# Only_pH.net
KiCad netlist of a schematic drawn in Altium Designer
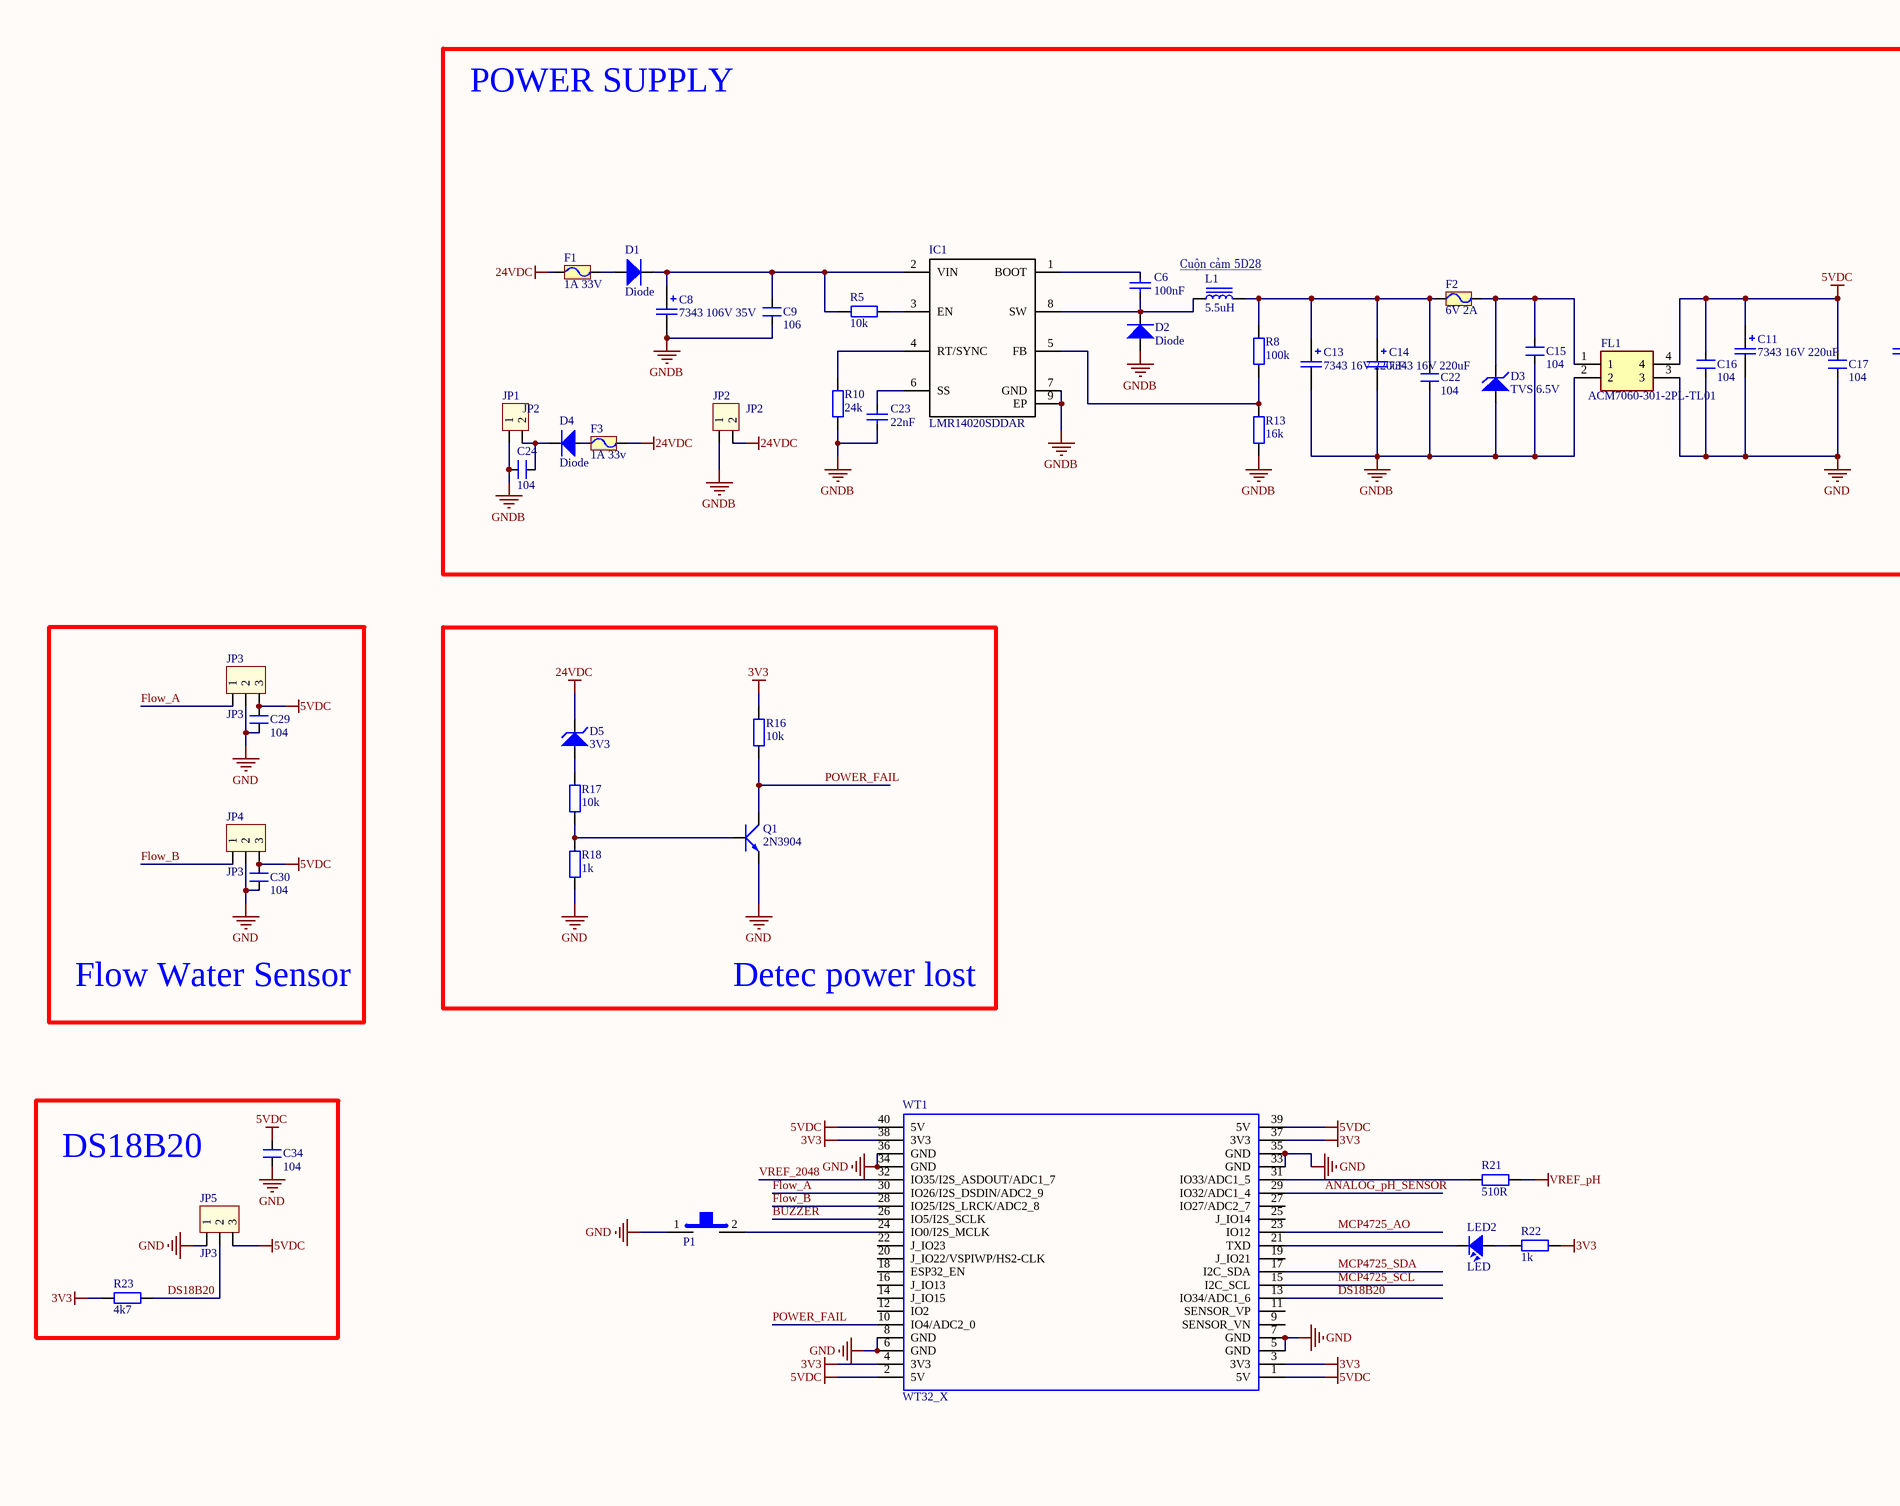
[diagram p0: Only_pH.SchDoc, left]
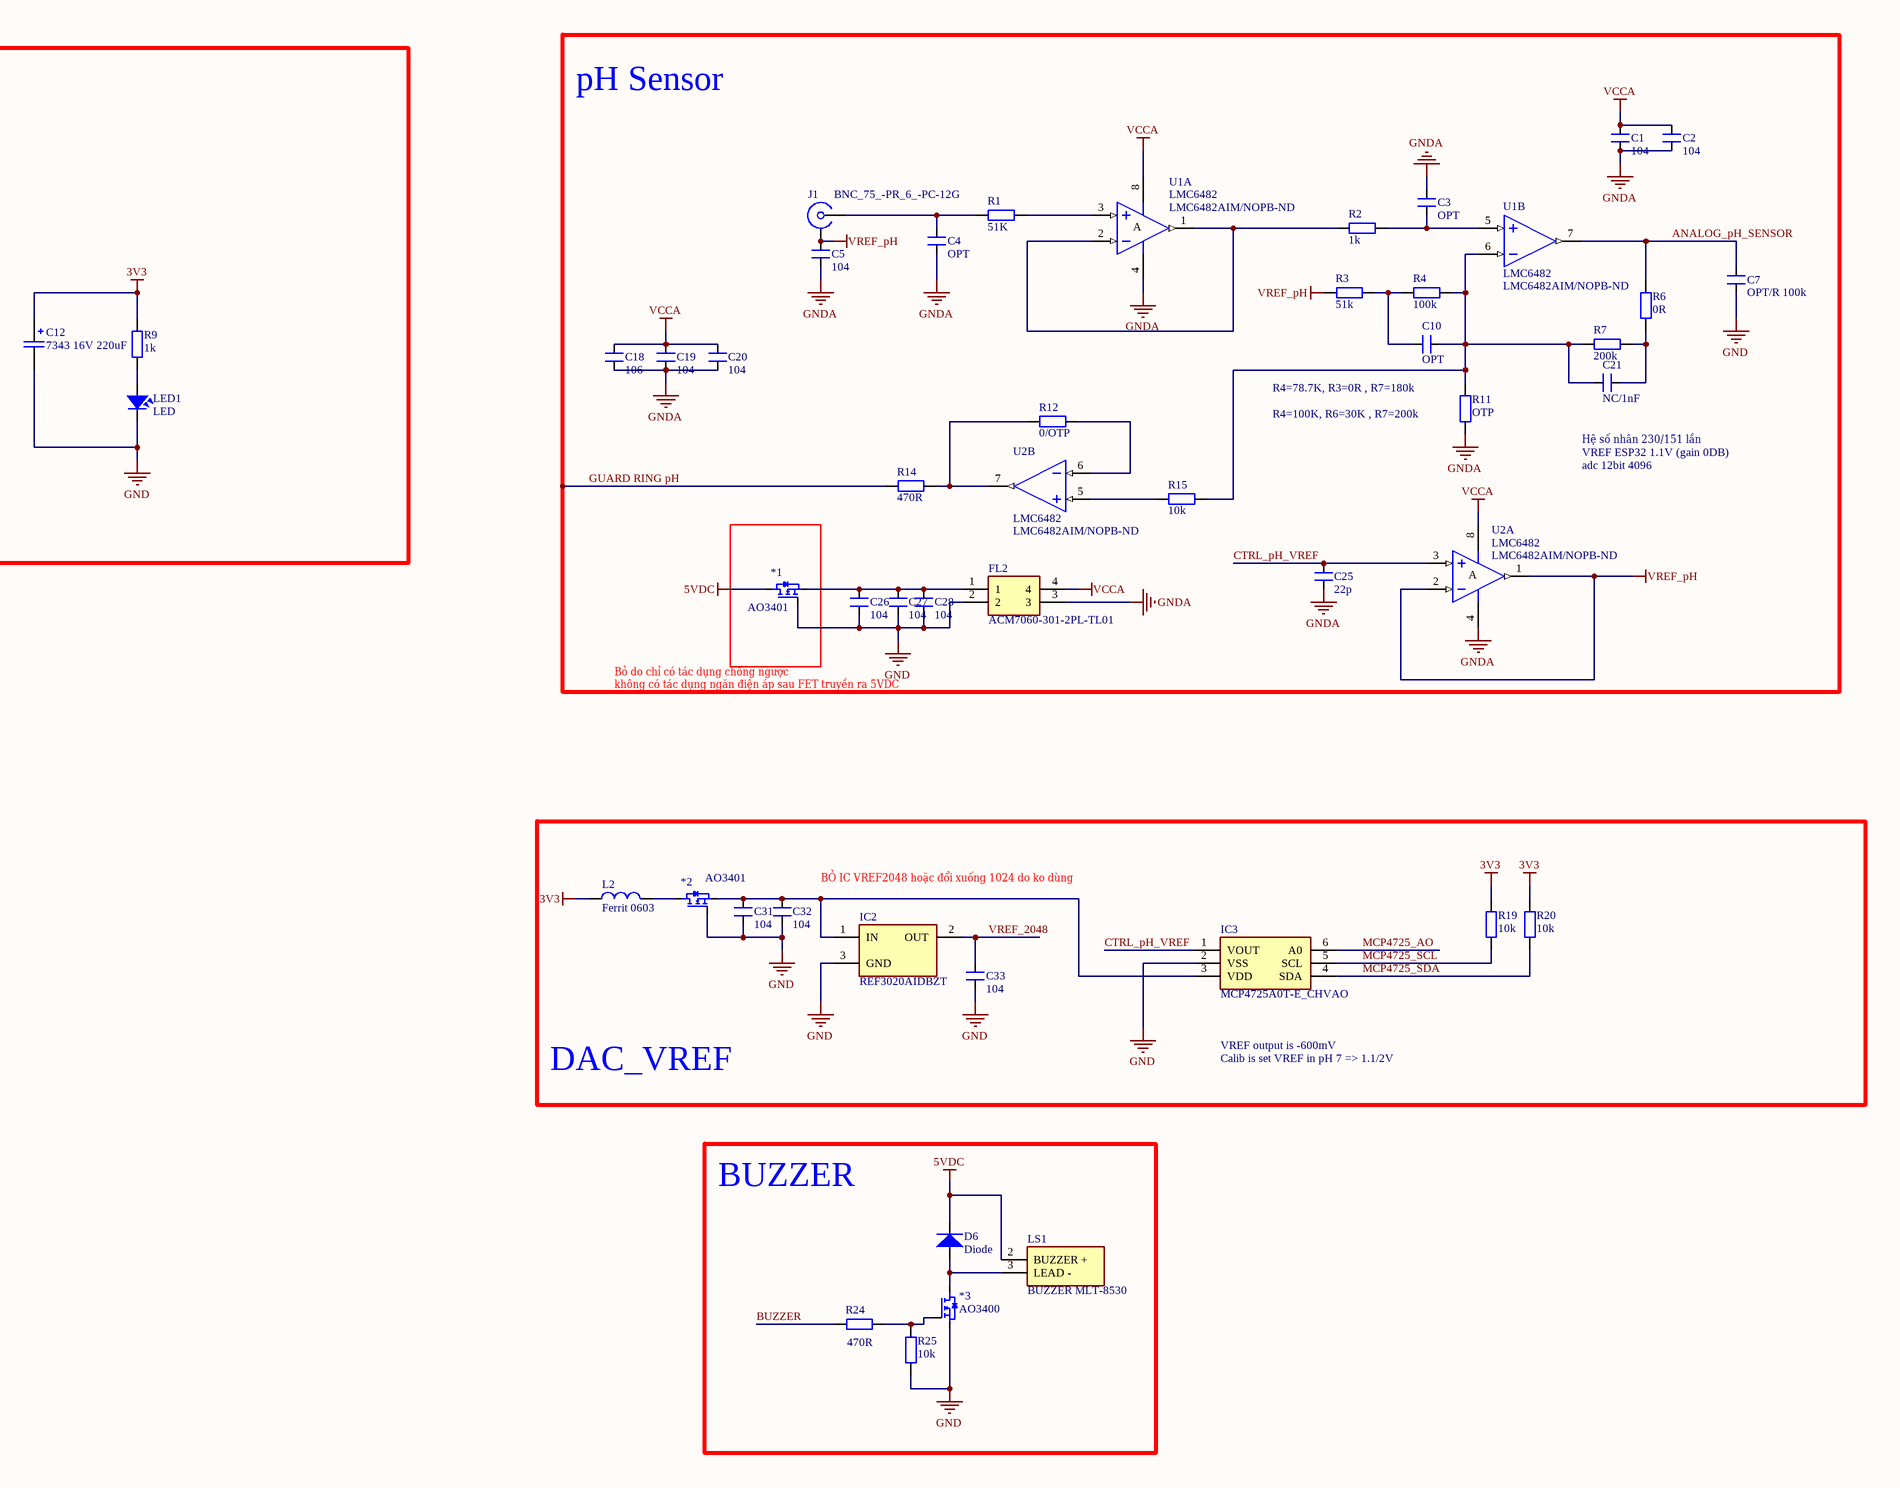
[diagram p1: Only_pH.SchDoc, right]

(export (version "E")
  (design (tool "Eeschema 10.0.6"))
  (components
    (comp (ref "*1") (value "AO3401") (footprint "SOT23-123") (libsource (lib "OBIT_TESLA") (part "AO3401")))
    (comp (ref "*2") (value "AO3401") (footprint "SOT23-123") (libsource (lib "OBIT_TESLA") (part "AO3401")))
    (comp (ref "*3") (value "AO3400") (footprint "SOT23-123") (libsource (lib "OBIT_TESLA") (part "AO3400")))
    (comp (ref "C1")
      (value "104")
      (footprint "SM-0805")
      (description "Cap SMD")
      (libsource (lib "OBIT_TESLA") (part "CM"))
    )
    (comp (ref "C2")
      (value "104")
      (footprint "SM-0805")
      (description "Cap SMD")
      (libsource (lib "OBIT_TESLA") (part "CM"))
    )
    (comp (ref "C3")
      (value "OPT")
      (footprint "CAPC-0603 (1608)")
      (description "Cap SMD")
      (libsource (lib "OBIT_TESLA") (part "CM"))
    )
    (comp (ref "C4")
      (value "OPT")
      (footprint "CAPC-0603 (1608)")
      (description "Cap SMD")
      (libsource (lib "OBIT_TESLA") (part "CM"))
    )
    (comp (ref "C5")
      (value "104")
      (footprint "SM-0805")
      (description "Cap SMD")
      (libsource (lib "OBIT_TESLA") (part "CM"))
    )
    (comp (ref "C6")
      (value "100nF")
      (footprint "SM-0603")
      (libsource (lib "AltiumLibraryTieuBao (1)") (part "CAP_NP"))
    )
    (comp (ref "C7")
      (value "OPT/R 100k")
      (footprint "CAPC-0603 (1608)")
      (description "Cap SMD")
      (libsource (lib "OBIT_TESLA") (part "CM"))
    )
    (comp (ref "C8")
      (value "7343 106V 35V")
      (footprint "CAP_TANTAL_2917(7343-31)")
      (fields (field (name "MPN") "TAJD107K016RNJ"))
      (libsource (lib "BYTECH_HW_LIB_2019") (part "TAJD107K016RNJ"))
    )
    (comp (ref "C9")
      (value "106")
      (footprint "SM-0805")
      (description "Cap SMD")
      (libsource (lib "OBIT_TESLA") (part "CM"))
    )
    (comp (ref "C10")
      (value "OPT")
      (footprint "CAPC-0603 (1608)")
      (description "Cap SMD")
      (libsource (lib "OBIT_TESLA") (part "CM"))
    )
    (comp (ref "C11")
      (value "7343 16V 220uF")
      (footprint "CAP_TANTAL_2917(7343-31)")
      (description "http://linhkienviet.vn/tu-tantalum-16v-220uf-7343")
      (fields (field (name "MPN") "TAJD107K016RNJ"))
      (libsource (lib "BYTECH_HW_LIB_2019") (part "TAJD107K016RNJ"))
    )
    (comp (ref "C12")
      (value "7343 16V 220uF")
      (footprint "CAP_TANTAL_2917(7343-31)")
      (description "http://linhkienviet.vn/tu-tantalum-16v-220uf-7343")
      (fields (field (name "MPN") "TAJD107K016RNJ"))
      (libsource (lib "BYTECH_HW_LIB_2019") (part "TAJD107K016RNJ"))
    )
    (comp (ref "C13")
      (value "7343 16V 220uF")
      (footprint "CAP_TANTAL_2917(7343-31)")
      (description "http://linhkienviet.vn/tu-tantalum-16v-220uf-7343")
      (fields (field (name "MPN") "TAJD107K016RNJ"))
      (libsource (lib "BYTECH_HW_LIB_2019") (part "TAJD107K016RNJ"))
    )
    (comp (ref "C14")
      (value "7343 16V 220uF")
      (footprint "CAP_TANTAL_2917(7343-31)")
      (description "http://linhkienviet.vn/tu-tantalum-16v-220uf-7343")
      (fields (field (name "MPN") "TAJD107K016RNJ"))
      (libsource (lib "BYTECH_HW_LIB_2019") (part "TAJD107K016RNJ"))
    )
    (comp (ref "C15")
      (value "104")
      (footprint "SM-0805")
      (description "Cap SMD")
      (libsource (lib "OBIT_TESLA") (part "CM"))
    )
    (comp (ref "C16")
      (value "104")
      (footprint "SM-0805")
      (description "Cap SMD")
      (libsource (lib "OBIT_TESLA") (part "CM"))
    )
    (comp (ref "C17")
      (value "104")
      (footprint "SM-0805")
      (description "Cap SMD")
      (libsource (lib "OBIT_TESLA") (part "CM"))
    )
    (comp (ref "C18")
      (value "106")
      (footprint "SM-0805")
      (description "Cap SMD")
      (libsource (lib "OBIT_TESLA") (part "CM"))
    )
    (comp (ref "C19")
      (value "104")
      (footprint "SM-0805")
      (description "Cap SMD")
      (libsource (lib "OBIT_TESLA") (part "CM"))
    )
    (comp (ref "C20")
      (value "104")
      (footprint "SM-0805")
      (description "Cap SMD")
      (libsource (lib "OBIT_TESLA") (part "CM"))
    )
    (comp (ref "C21")
      (value "NC/1nF")
      (footprint "CAPC-0603 (1608)")
      (description "Cap SMD")
      (libsource (lib "OBIT_TESLA") (part "CM"))
    )
    (comp (ref "C22")
      (value "104")
      (footprint "SM-0805")
      (description "Cap SMD")
      (libsource (lib "OBIT_TESLA") (part "CM"))
    )
    (comp (ref "C23")
      (value "22nF")
      (footprint "SM-0603")
      (libsource (lib "AltiumLibraryTieuBao (1)") (part "CAP_NP"))
    )
    (comp (ref "C24")
      (value "104")
      (footprint "SM-0805")
      (description "Cap SMD")
      (libsource (lib "OBIT_TESLA") (part "CM"))
    )
    (comp (ref "C25")
      (value "22p")
      (footprint "SM-0805")
      (description "Cap SMD")
      (libsource (lib "OBIT_TESLA") (part "CM"))
    )
    (comp (ref "C26")
      (value "104")
      (footprint "SM-0805")
      (description "Cap SMD")
      (libsource (lib "OBIT_TESLA") (part "CM"))
    )
    (comp (ref "C27")
      (value "104")
      (footprint "SM-0805")
      (description "Cap SMD")
      (libsource (lib "OBIT_TESLA") (part "CM"))
    )
    (comp (ref "C28")
      (value "104")
      (footprint "SM-0805")
      (description "Cap SMD")
      (libsource (lib "OBIT_TESLA") (part "CM"))
    )
    (comp (ref "C29")
      (value "104")
      (footprint "SM-0805")
      (description "Cap SMD")
      (libsource (lib "OBIT_TESLA") (part "CM"))
    )
    (comp (ref "C30")
      (value "104")
      (footprint "SM-0805")
      (description "Cap SMD")
      (libsource (lib "OBIT_TESLA") (part "CM"))
    )
    (comp (ref "C31")
      (value "104")
      (footprint "SM-0805")
      (description "Cap SMD")
      (libsource (lib "OBIT_TESLA") (part "CM"))
    )
    (comp (ref "C32")
      (value "104")
      (footprint "SM-0805")
      (description "Cap SMD")
      (libsource (lib "OBIT_TESLA") (part "CM"))
    )
    (comp (ref "C33")
      (value "104")
      (footprint "SM-0603")
      (description "Cap SMD")
      (libsource (lib "OBIT_TESLA") (part "CM"))
    )
    (comp (ref "C34")
      (value "104")
      (footprint "SM-0805")
      (description "Cap SMD")
      (libsource (lib "OBIT_TESLA") (part "CM"))
    )
    (comp (ref "D1") (value "Diode") (footprint "DIO-SMD-106") (libsource (lib "OBIT_TESLA") (part "Diode")))
    (comp (ref "D2") (value "Diode") (footprint "DIO-SMD-106") (libsource (lib "OBIT_TESLA") (part "Diode")))
    (comp (ref "D3")
      (value "TVS 6.5V")
      (footprint "DIO-SMD-106")
      (description "Diode Zener")
      (fields (field (name "PART NUMBER") "BZV55-C5V1"))
      (libsource (lib "OBIT_TESLA") (part "Diode Zener"))
    )
    (comp (ref "D4") (value "Diode") (footprint "DIO-SMD-106") (libsource (lib "OBIT_TESLA") (part "Diode")))
    (comp (ref "D5")
      (value "3V3")
      (footprint "DIO-SMD-106")
      (description "Diode Zener")
      (fields (field (name "PART NUMBER") "BZV55-C5V1"))
      (libsource (lib "OBIT_TESLA") (part "Diode Zener"))
    )
    (comp (ref "D6") (value "Diode") (footprint "DIO-SMD-123") (libsource (lib "") (part "Diode_1")))
    (comp (ref "F1")
      (value "1A 33V")
      (footprint "RES-SMD-1812")
      (libsource (lib "OBIT_TESLA") (part "FUSE_1"))
    )
    (comp (ref "F2")
      (value "6V 2A")
      (footprint "RES-SMD-1812")
      (libsource (lib "OBIT_TESLA") (part "FUSE_1"))
    )
    (comp (ref "F3")
      (value "1A 33v")
      (footprint "RES-SMD-1812")
      (libsource (lib "OBIT_TESLA") (part "FUSE_1"))
    )
    (comp (ref "FL1")
      (value "ACM7060-301-2PL-TL01")
      (footprint "ACM70603012PLTL01")
      (description "Filter")
      (fields (field (name "MOUSER PART NUMBER") "810-ACM7063012PLTL01"))
      (libsource (lib "OBIT_TESLA") (part "ACM7060-301-2PL-TL01"))
    )
    (comp (ref "FL2")
      (value "ACM7060-301-2PL-TL01")
      (footprint "ACM70603012PLTL01")
      (description "Filter")
      (fields (field (name "MOUSER PART NUMBER") "810-ACM7063012PLTL01"))
      (libsource (lib "OBIT_TESLA") (part "ACM7060-301-2PL-TL01"))
    )
    (comp (ref "IC1")
      (value "LMR14020SDDAR")
      (footprint "SOIC127P600X170-9N")
      (description "Integrated Circuit")
      (fields (field (name "MOUSER PART NUMBER") "595-LMR14020SDDAR"))
      (libsource (lib "OBIT_TESLA") (part "LMR14020SDDAR"))
    )
    (comp (ref "IC2")
      (value "REF3020AIDBZT")
      (footprint "SOT95P237X112-3N")
      (description "Integrated Circuit")
      (fields (field (name "MOUSER PART NUMBER") "595-REF3020AIDBZT"))
      (libsource (lib "OBIT_TESLA") (part "REF3020AIDBZT"))
    )
    (comp (ref "IC3")
      (value "MCP4725A0T-E_CHVAO")
      (footprint "SOT95P270X145-6N")
      (description "Integrated Circuit")
      (fields
        (field (name "MANUFACTURER_PART_NUMBER") "MCP4725A0T-E/CHVAO")
        (field (name "MOUSER PART NUMBER") "579-MCP4725A0TECHVAO")
      )
      (libsource (lib "OBIT_TESLA") (part "MCP4725A0T-E_CHVAO"))
    )
    (comp (ref "J1")
      (value "BNC_75_-PR_6_-PC-12G")
      (footprint "BNC75PR6PC12G")
      (description "Connector")
      (fields
        (field (name "MANUFACTURER_PART_NUMBER") "BNC(75)-PR(6)-PC-12G")
        (field (name "MOUSER PART NUMBER") "798-BNC75-PR6-PC-12G")
      )
      (libsource (lib "OBIT_TESLA") (part "BNC_75_-PR_6_-PC-12G"))
    )
    (comp (ref "JP1")
      (value "JP2")
      (footprint "CON2")
      (description "Connector 2")
      (libsource (lib "OBIT_TESLA") (part "Con2"))
    )
    (comp (ref "JP2")
      (value "JP2")
      (footprint "CON2")
      (description "Connector 2")
      (libsource (lib "OBIT_TESLA") (part "Con2"))
    )
    (comp (ref "JP3")
      (value "JP3")
      (footprint "CON3")
      (description "Connector 3")
      (libsource (lib "OBIT_TESLA") (part "Con3"))
    )
    (comp (ref "JP4")
      (value "JP3")
      (footprint "CON3")
      (description "Connector 3")
      (libsource (lib "OBIT_TESLA") (part "Con3"))
    )
    (comp (ref "JP5")
      (value "JP3")
      (footprint "CON3")
      (description "Connector 3")
      (libsource (lib "OBIT_TESLA") (part "Con3"))
    )
    (comp (ref "L1")
      (value "5.5uH")
      (footprint "WURTH WE-HCI 7040")
      (description "SMT Inductor")
      (libsource (lib "OBIT_TESLA") (part "Inductor_3"))
    )
    (comp (ref "L2")
      (value "Ferrit 0603")
      (footprint "IND-0603 (1608)")
      (description "FIXED IND 10UH 60MA 700 MOHM SMD")
      (fields (field (name "MPN") "LB1608T100M"))
      (libsource (lib "OBIT_TESLA") (part "LB1608T100M"))
    )
    (comp (ref "LED1")
      (value "LED")
      (footprint "SM-LED-0805-Blue")
      (libsource (lib "OBIT_TESLA") (part "LED"))
    )
    (comp (ref "LED2")
      (value "LED")
      (footprint "SM-LED-0805-Blue")
      (libsource (lib "OBIT_TESLA") (part "LED"))
    )
    (comp (ref "LS1")
      (value "BUZZER MLT-8530")
      (footprint "MLT8530")
      (description "Loudspeaker or Buzzer")
      (fields (field (name "MANUFACTURER_PART_NUMBER") "MLT-8530"))
      (libsource (lib "OBIT_TESLA") (part "BUZZER MLT-8530"))
    )
    (comp (ref "P1")
      (value "~")
      (footprint "SW 2P SMD")
      (description "SMD Mini Push Button Switch 2 Pin 3x6x2.7mm")
      (fields (field (name "MPN") "SMD Mini Push Button 2 SMD"))
      (libsource (lib "OBIT_TESLA") (part "Button 2 SMD"))
    )
    (comp (ref "Q1")
      (value "2N3904")
      (footprint "SOT23-231")
      (description "NPN 600mW, ECB")
      (libsource (lib "OBIT_TESLA") (part "2N3904"))
    )
    (comp (ref "R1")
      (value "51K")
      (footprint "RES-SMD-0603")
      (description "Resistor R1/4W")
      (libsource (lib "OBIT_TESLA") (part "R"))
    )
    (comp (ref "R2")
      (value "1k")
      (footprint "RES-SMD-0603")
      (description "Resistor R1/4W")
      (libsource (lib "OBIT_TESLA") (part "R"))
    )
    (comp (ref "R3")
      (value "51k")
      (footprint "RES-SMD-0603")
      (description "Resistor R1/4W")
      (libsource (lib "OBIT_TESLA") (part "R"))
    )
    (comp (ref "R4")
      (value "100k")
      (footprint "RES-SMD-0603")
      (description "Resistor R1/4W")
      (libsource (lib "OBIT_TESLA") (part "R"))
    )
    (comp (ref "R5")
      (value "10k")
      (footprint "RES-SMD-0603")
      (description "Resistor R1/4W")
      (libsource (lib "OBIT_TESLA") (part "R"))
    )
    (comp (ref "R6")
      (value "0R")
      (footprint "RES-SMD-0603")
      (description "Resistor R1/4W")
      (libsource (lib "OBIT_TESLA") (part "R"))
    )
    (comp (ref "R7")
      (value "200k")
      (footprint "RES-SMD-0603")
      (description "Resistor R1/4W")
      (libsource (lib "OBIT_TESLA") (part "R"))
    )
    (comp (ref "R8")
      (value "100k")
      (footprint "RES-SMD-0603")
      (description "Resistor R1/4W")
      (libsource (lib "OBIT_TESLA") (part "R"))
    )
    (comp (ref "R9")
      (value "1k")
      (footprint "RES-SMD-0603")
      (description "Resistor R1/4W")
      (libsource (lib "OBIT_TESLA") (part "R"))
    )
    (comp (ref "R10")
      (value "24k")
      (footprint "RES-SMD-0603")
      (description "Resistor R1/4W")
      (libsource (lib "OBIT_TESLA") (part "R"))
    )
    (comp (ref "R11")
      (value "OTP")
      (footprint "RES-SMD-0603")
      (description "Resistor R1/4W")
      (libsource (lib "OBIT_TESLA") (part "R"))
    )
    (comp (ref "R12")
      (value "0/OTP")
      (footprint "RES-SMD-0603")
      (description "Resistor R1/4W")
      (libsource (lib "OBIT_TESLA") (part "R"))
    )
    (comp (ref "R13")
      (value "16k")
      (footprint "RES-SMD-0603")
      (description "Resistor R1/4W")
      (libsource (lib "OBIT_TESLA") (part "R"))
    )
    (comp (ref "R14")
      (value "470R")
      (footprint "RES-SMD-0603")
      (description "Resistor R1/4W")
      (libsource (lib "OBIT_TESLA") (part "R"))
    )
    (comp (ref "R15")
      (value "10k")
      (footprint "RES-SMD-0603")
      (description "Resistor R1/4W")
      (libsource (lib "OBIT_TESLA") (part "R"))
    )
    (comp (ref "R16")
      (value "10k")
      (footprint "RES-SMD-0603")
      (description "Resistor R1/4W")
      (libsource (lib "OBIT_TESLA") (part "R"))
    )
    (comp (ref "R17")
      (value "10k")
      (footprint "RES-SMD-0603")
      (description "Resistor R1/4W")
      (libsource (lib "OBIT_TESLA") (part "R"))
    )
    (comp (ref "R18")
      (value "1k")
      (footprint "RES-SMD-0603")
      (description "Resistor R1/4W")
      (libsource (lib "OBIT_TESLA") (part "R"))
    )
    (comp (ref "R19")
      (value "10k")
      (footprint "RES-SMD-0603")
      (description "Resistor R1/4W")
      (libsource (lib "OBIT_TESLA") (part "R"))
    )
    (comp (ref "R20")
      (value "10k")
      (footprint "RES-SMD-0603")
      (description "Resistor R1/4W")
      (libsource (lib "OBIT_TESLA") (part "R"))
    )
    (comp (ref "R21")
      (value "510R")
      (footprint "RES-SMD-0603")
      (description "Resistor R1/4W")
      (libsource (lib "OBIT_TESLA") (part "R"))
    )
    (comp (ref "R22")
      (value "1k")
      (footprint "RES-SMD-0603")
      (description "Resistor R1/4W")
      (libsource (lib "OBIT_TESLA") (part "R"))
    )
    (comp (ref "R23")
      (value "4k7")
      (footprint "RES-SMD-0603")
      (description "Resistor R1/4W")
      (libsource (lib "OBIT_TESLA") (part "R"))
    )
    (comp (ref "R24")
      (value "470R")
      (footprint "RES-SMD-0603")
      (description "Resistor R1/4W")
      (libsource (lib "OBIT_TESLA") (part "R"))
    )
    (comp (ref "R25")
      (value "10k")
      (footprint "RES-SMD-0603")
      (description "Resistor R1/4W")
      (libsource (lib "OBIT_TESLA") (part "R"))
    )
    (comp (ref "U1")
      (value "LMC6482")
      (footprint "SOIC-8")
      (description "LMC6482 CMOS Dual Rail-to-Rail Input and Output Operational Amplifier")
      (fields (field (name "MFR") "Ti") (field (name "SUPPLIER PART NUMBER 1") "LMC6482AIM/NOPB-ND"))
      (libsource (lib "OBIT_TESLA") (part "LMC6482"))
    )
    (comp (ref "U2")
      (value "LMC6482")
      (footprint "SOIC-8")
      (description "LMC6482 CMOS Dual Rail-to-Rail Input and Output Operational Amplifier")
      (fields (field (name "MFR") "Ti") (field (name "SUPPLIER PART NUMBER 1") "LMC6482AIM/NOPB-ND"))
      (libsource (lib "OBIT_TESLA") (part "LMC6482"))
    )
    (comp (ref "WT1")
      (value "WT32_X")
      (footprint "WT32_SC01_Sheild")
      (libsource (lib "OBIT_TESLA") (part "WT32-SC01"))
    )
  )
  (nets
    (net (code "1") (name "/ANALOG_pH_SENSOR") (class "Default")
      (node (ref "C7") (pin "1") (pinfunction "1_1") (pintype "passive"))
      (node (ref "R6") (pin "1") (pinfunction "1_1") (pintype "passive"))
      (node (ref "U1") (pin "7") (pinfunction "OUT_7") (pintype "output"))
      (node (ref "WT1") (pin "29") (pinfunction "IO32/ADC1_4_29") (pintype "passive"))
    )
    (net (code "2") (name "/BUZZER") (class "Default")
      (node (ref "R24") (pin "2") (pinfunction "2_2") (pintype "passive"))
      (node (ref "WT1") (pin "26") (pinfunction "IO5/I2S_SCLK_26") (pintype "passive"))
    )
    (net (code "3") (name "/CTRL_pH_VREF") (class "Default")
      (node (ref "C25") (pin "1") (pinfunction "1_1") (pintype "passive"))
      (node (ref "IC3") (pin "1") (pinfunction "VOUT_1") (pintype "passive"))
      (node (ref "U2") (pin "3") (pinfunction "IN+_3") (pintype "input"))
    )
    (net (code "5") (name "/DS18B20") (class "Default")
      (node (ref "JP5") (pin "2") (pinfunction "2_2") (pintype "passive"))
      (node (ref "R23") (pin "2") (pinfunction "2_2") (pintype "passive"))
      (node (ref "WT1") (pin "13") (pinfunction "IO34/ADC1_6_13") (pintype "passive"))
    )
    (net (code "8") (name "/Flow_A") (class "Default")
      (node (ref "JP3") (pin "1") (pinfunction "1_1") (pintype "passive"))
      (node (ref "WT1") (pin "30") (pinfunction "IO26/I2S_DSDIN/ADC2_9_30") (pintype "passive"))
    )
    (net (code "9") (name "/Flow_B") (class "Default")
      (node (ref "JP4") (pin "1") (pinfunction "1_1") (pintype "passive"))
      (node (ref "WT1") (pin "28") (pinfunction "IO25/I2S_LRCK/ADC2_8_28") (pintype "passive"))
    )
    (net (code "10") (name "/GUARD RING pH") (class "Default")
      (node (ref "R14") (pin "2") (pinfunction "2_2") (pintype "passive"))
    )
    (net (code "11") (name "/MCP4725_AO") (class "Default")
      (node (ref "IC3") (pin "6") (pinfunction "A0_6") (pintype "passive"))
      (node (ref "WT1") (pin "23") (pinfunction "IO12_23") (pintype "passive"))
    )
    (net (code "12") (name "/MCP4725_SCL") (class "Default")
      (node (ref "IC3") (pin "5") (pinfunction "SCL_5") (pintype "passive"))
      (node (ref "R19") (pin "2") (pinfunction "2_2") (pintype "passive"))
      (node (ref "WT1") (pin "15") (pinfunction "I2C_SCL_15") (pintype "passive"))
    )
    (net (code "13") (name "/MCP4725_SDA") (class "Default")
      (node (ref "IC3") (pin "4") (pinfunction "SDA_4") (pintype "passive"))
      (node (ref "R20") (pin "2") (pinfunction "2_2") (pintype "passive"))
      (node (ref "WT1") (pin "17") (pinfunction "I2C_SDA_17") (pintype "passive"))
    )
    (net (code "15") (name "/POWER_FAIL") (class "Default")
      (node (ref "Q1") (pin "3") (pinfunction "C_3") (pintype "passive"))
      (node (ref "R16") (pin "2") (pinfunction "2_2") (pintype "passive"))
      (node (ref "WT1") (pin "10") (pinfunction "IO4/ADC2_0_10") (pintype "passive"))
    )
    (net (code "16") (name "/VREF_2048") (class "Default")
      (node (ref "C33") (pin "2") (pinfunction "2_2") (pintype "passive"))
      (node (ref "IC2") (pin "2") (pinfunction "OUT_2") (pintype "passive"))
      (node (ref "WT1") (pin "32") (pinfunction "IO35/I2S_ASDOUT/ADC1_7_32") (pintype "passive"))
    )
    (net (code "18") (name "3V3") (class "Default")
      (node (ref "C12") (pin "1") (pinfunction "1_1") (pintype "passive"))
      (node (ref "L2") (pin "1") (pinfunction "1_1") (pintype "passive"))
      (node (ref "R16") (pin "1") (pinfunction "1_1") (pintype "passive"))
      (node (ref "R19") (pin "1") (pinfunction "1_1") (pintype "passive"))
      (node (ref "R20") (pin "1") (pinfunction "1_1") (pintype "passive"))
      (node (ref "R22") (pin "2") (pinfunction "2_2") (pintype "passive"))
      (node (ref "R23") (pin "1") (pinfunction "1_1") (pintype "passive"))
      (node (ref "R9") (pin "2") (pinfunction "2_2") (pintype "passive"))
      (node (ref "WT1") (pin "3") (pinfunction "3V3_3") (pintype "passive"))
      (node (ref "WT1") (pin "37") (pinfunction "3V3_37") (pintype "passive"))
      (node (ref "WT1") (pin "38") (pinfunction "3V3_38") (pintype "passive"))
      (node (ref "WT1") (pin "4") (pinfunction "3V3_4") (pintype "passive"))
    )
    (net (code "19") (name "5VDC") (class "Default")
      (node (ref "*1") (pin "2") (pintype "passive"))
      (node (ref "C11") (pin "1") (pinfunction "1_1") (pintype "passive"))
      (node (ref "C16") (pin "2") (pinfunction "2_2") (pintype "passive"))
      (node (ref "C17") (pin "2") (pinfunction "2_2") (pintype "passive"))
      (node (ref "C29") (pin "2") (pinfunction "2_2") (pintype "passive"))
      (node (ref "C30") (pin "2") (pinfunction "2_2") (pintype "passive"))
      (node (ref "C34") (pin "2") (pinfunction "2_2") (pintype "passive"))
      (node (ref "D6") (pin "2") (pinfunction "2_2") (pintype "passive"))
      (node (ref "FL1") (pin "4") (pinfunction "4_4") (pintype "passive"))
      (node (ref "JP3") (pin "3") (pinfunction "3_3") (pintype "passive"))
      (node (ref "JP4") (pin "3") (pinfunction "3_3") (pintype "passive"))
      (node (ref "JP5") (pin "3") (pinfunction "3_3") (pintype "passive"))
      (node (ref "LS1") (pin "2") (pinfunction "BUZZER_+_2") (pintype "passive"))
      (node (ref "WT1") (pin "1") (pinfunction "5V_1") (pintype "passive"))
      (node (ref "WT1") (pin "2") (pinfunction "5V_2") (pintype "passive"))
      (node (ref "WT1") (pin "39") (pinfunction "5V_39") (pintype "passive"))
      (node (ref "WT1") (pin "40") (pinfunction "5V_40") (pintype "passive"))
    )
    (net (code "20") (name "24VDC") (class "Default")
      (node (ref "D5") (pin "2") (pinfunction "2_2") (pintype "passive"))
      (node (ref "F1") (pin "2") (pinfunction "2_2") (pintype "passive"))
      (node (ref "F3") (pin "1") (pinfunction "1_1") (pintype "passive"))
      (node (ref "JP2") (pin "2") (pinfunction "2_2") (pintype "passive"))
    )
    (net (code "21") (name "GND") (class "Default")
      (node (ref "*1") (pin "1") (pintype "passive"))
      (node (ref "*2") (pin "1") (pintype "passive"))
      (node (ref "*3") (pin "3") (pintype "passive"))
      (node (ref "C11") (pin "2") (pinfunction "2_2") (pintype "passive"))
      (node (ref "C12") (pin "2") (pinfunction "2_2") (pintype "passive"))
      (node (ref "C16") (pin "1") (pinfunction "1_1") (pintype "passive"))
      (node (ref "C17") (pin "1") (pinfunction "1_1") (pintype "passive"))
      (node (ref "C26") (pin "2") (pinfunction "2_2") (pintype "passive"))
      (node (ref "C27") (pin "2") (pinfunction "2_2") (pintype "passive"))
      (node (ref "C28") (pin "2") (pinfunction "2_2") (pintype "passive"))
      (node (ref "C29") (pin "1") (pinfunction "1_1") (pintype "passive"))
      (node (ref "C30") (pin "1") (pinfunction "1_1") (pintype "passive"))
      (node (ref "C31") (pin "2") (pinfunction "2_2") (pintype "passive"))
      (node (ref "C32") (pin "2") (pinfunction "2_2") (pintype "passive"))
      (node (ref "C33") (pin "1") (pinfunction "1_1") (pintype "passive"))
      (node (ref "C34") (pin "1") (pinfunction "1_1") (pintype "passive"))
      (node (ref "C7") (pin "2") (pinfunction "2_2") (pintype "passive"))
      (node (ref "FL1") (pin "3") (pinfunction "3_3") (pintype "passive"))
      (node (ref "FL2") (pin "2") (pinfunction "2_2") (pintype "passive"))
      (node (ref "IC2") (pin "3") (pinfunction "GND_3") (pintype "passive"))
      (node (ref "IC3") (pin "2") (pinfunction "VSS_2") (pintype "passive"))
      (node (ref "JP3") (pin "2") (pinfunction "2_2") (pintype "passive"))
      (node (ref "JP4") (pin "2") (pinfunction "2_2") (pintype "passive"))
      (node (ref "JP5") (pin "1") (pinfunction "1_1") (pintype "passive"))
      (node (ref "LED1") (pin "2") (pinfunction "2_2") (pintype "passive"))
      (node (ref "P1") (pin "1") (pinfunction "1_1") (pintype "passive"))
      (node (ref "Q1") (pin "1") (pinfunction "E_1") (pintype "passive"))
      (node (ref "R18") (pin "2") (pinfunction "2_2") (pintype "passive"))
      (node (ref "R25") (pin "1") (pinfunction "1_1") (pintype "passive"))
      (node (ref "WT1") (pin "33") (pinfunction "GND_33") (pintype "passive"))
      (node (ref "WT1") (pin "34") (pinfunction "GND_34") (pintype "passive"))
      (node (ref "WT1") (pin "35") (pinfunction "GND_35") (pintype "passive"))
      (node (ref "WT1") (pin "36") (pinfunction "GND_36") (pintype "passive"))
      (node (ref "WT1") (pin "5") (pinfunction "GND_5") (pintype "passive"))
      (node (ref "WT1") (pin "6") (pinfunction "GND_6") (pintype "passive"))
      (node (ref "WT1") (pin "7") (pinfunction "GND_7") (pintype "passive"))
      (node (ref "WT1") (pin "8") (pinfunction "GND_8") (pintype "passive"))
    )
    (net (code "22") (name "GNDA") (class "Default")
      (node (ref "C1") (pin "2") (pinfunction "2_2") (pintype "passive"))
      (node (ref "C18") (pin "2") (pinfunction "2_2") (pintype "passive"))
      (node (ref "C19") (pin "2") (pinfunction "2_2") (pintype "passive"))
      (node (ref "C2") (pin "2") (pinfunction "2_2") (pintype "passive"))
      (node (ref "C20") (pin "2") (pinfunction "2_2") (pintype "passive"))
      (node (ref "C25") (pin "2") (pinfunction "2_2") (pintype "passive"))
      (node (ref "C3") (pin "1") (pinfunction "1_1") (pintype "passive"))
      (node (ref "C4") (pin "2") (pinfunction "2_2") (pintype "passive"))
      (node (ref "C5") (pin "1") (pinfunction "1_1") (pintype "passive"))
      (node (ref "FL2") (pin "3") (pinfunction "3_3") (pintype "passive"))
      (node (ref "R11") (pin "2") (pinfunction "2_2") (pintype "passive"))
      (node (ref "U1") (pin "4") (pinfunction "V-_4") (pintype "power_in"))
      (node (ref "U2") (pin "4") (pinfunction "V-_4") (pintype "power_in"))
    )
    (net (code "23") (name "GNDB") (class "Default")
      (node (ref "C13") (pin "2") (pinfunction "2_2") (pintype "passive"))
      (node (ref "C14") (pin "2") (pinfunction "2_2") (pintype "passive"))
      (node (ref "C15") (pin "1") (pinfunction "1_1") (pintype "passive"))
      (node (ref "C22") (pin "1") (pinfunction "1_1") (pintype "passive"))
      (node (ref "C23") (pin "1") (pinfunction "1_1") (pintype "passive"))
      (node (ref "C24") (pin "2") (pinfunction "2_2") (pintype "passive"))
      (node (ref "C8") (pin "2") (pinfunction "2_2") (pintype "passive"))
      (node (ref "C9") (pin "1") (pinfunction "1_1") (pintype "passive"))
      (node (ref "D2") (pin "1") (pinfunction "1_1") (pintype "passive"))
      (node (ref "D3") (pin "1") (pinfunction "1_1") (pintype "passive"))
      (node (ref "FL1") (pin "2") (pinfunction "2_2") (pintype "passive"))
      (node (ref "IC1") (pin "7") (pinfunction "GND_7") (pintype "passive"))
      (node (ref "IC1") (pin "9") (pinfunction "EP_9") (pintype "passive"))
      (node (ref "JP1") (pin "1") (pinfunction "1_1") (pintype "passive"))
      (node (ref "JP2") (pin "1") (pinfunction "1_1") (pintype "passive"))
      (node (ref "R10") (pin "1") (pinfunction "1_1") (pintype "passive"))
      (node (ref "R13") (pin "2") (pinfunction "2_2") (pintype "passive"))
    )
    (net (code "24") (name "Net-(*1-Pad3)") (class "Default")
      (node (ref "*1") (pin "3") (pintype "passive"))
      (node (ref "C26") (pin "1") (pinfunction "1_1") (pintype "passive"))
      (node (ref "C27") (pin "1") (pinfunction "1_1") (pintype "passive"))
      (node (ref "C28") (pin "1") (pinfunction "1_1") (pintype "passive"))
      (node (ref "FL2") (pin "1") (pinfunction "1_1") (pintype "passive"))
    )
    (net (code "25") (name "Net-(*2-Pad2)") (class "Default")
      (node (ref "*2") (pin "2") (pintype "passive"))
      (node (ref "L2") (pin "2") (pinfunction "2_2") (pintype "passive"))
    )
    (net (code "26") (name "Net-(*3-Pad1)") (class "Default")
      (node (ref "*3") (pin "1") (pintype "passive"))
      (node (ref "R24") (pin "1") (pinfunction "1_1") (pintype "passive"))
      (node (ref "R25") (pin "2") (pinfunction "2_2") (pintype "passive"))
    )
    (net (code "27") (name "Net-(C4-Pad1)") (class "Default")
      (node (ref "C4") (pin "1") (pinfunction "1_1") (pintype "passive"))
      (node (ref "J1") (pin "1") (pinfunction "1_1") (pintype "passive"))
      (node (ref "R1") (pin "2") (pinfunction "2_2") (pintype "passive"))
    )
    (net (code "28") (name "Net-(C10-Pad1)") (class "Default")
      (node (ref "C10") (pin "1") (pinfunction "1_1") (pintype "passive"))
      (node (ref "R3") (pin "1") (pinfunction "1_1") (pintype "passive"))
      (node (ref "R4") (pin "2") (pinfunction "2_2") (pintype "passive"))
    )
    (net (code "29") (name "Net-(C13-Pad1)") (class "Default")
      (node (ref "C13") (pin "1") (pinfunction "1_1") (pintype "passive"))
      (node (ref "C14") (pin "1") (pinfunction "1_1") (pintype "passive"))
      (node (ref "C22") (pin "2") (pinfunction "2_2") (pintype "passive"))
      (node (ref "F2") (pin "2") (pinfunction "2_2") (pintype "passive"))
      (node (ref "L1") (pin "2") (pinfunction "2_2") (pintype "passive"))
      (node (ref "R8") (pin "1") (pinfunction "1_1") (pintype "passive"))
    )
    (net (code "30") (name "Net-(C15-Pad2)") (class "Default")
      (node (ref "C15") (pin "2") (pinfunction "2_2") (pintype "passive"))
      (node (ref "D3") (pin "2") (pinfunction "2_2") (pintype "passive"))
      (node (ref "F2") (pin "1") (pinfunction "1_1") (pintype "passive"))
      (node (ref "FL1") (pin "1") (pinfunction "1_1") (pintype "passive"))
    )
    (net (code "31") (name "Net-(C21-Pad2)") (class "Default")
      (node (ref "C21") (pin "2") (pinfunction "2_2") (pintype "passive"))
      (node (ref "R6") (pin "2") (pinfunction "2_2") (pintype "passive"))
      (node (ref "R7") (pin "1") (pinfunction "1_1") (pintype "passive"))
    )
    (net (code "32") (name "Net-(C24-Pad1)") (class "Default")
      (node (ref "C24") (pin "1") (pinfunction "1_1") (pintype "passive"))
      (node (ref "D4") (pin "2") (pinfunction "2_2") (pintype "passive"))
      (node (ref "JP1") (pin "2") (pinfunction "2_2") (pintype "passive"))
    )
    (net (code "33") (name "Net-(D1-Pad1)") (class "Default")
      (node (ref "D1") (pin "1") (pinfunction "1_1") (pintype "passive"))
      (node (ref "F1") (pin "1") (pinfunction "1_1") (pintype "passive"))
    )
    (net (code "34") (name "Net-(D4-Pad1)") (class "Default")
      (node (ref "D4") (pin "1") (pinfunction "1_1") (pintype "passive"))
      (node (ref "F3") (pin "2") (pinfunction "2_2") (pintype "passive"))
    )
    (net (code "35") (name "Net-(D5-Pad1)") (class "Default")
      (node (ref "D5") (pin "1") (pinfunction "1_1") (pintype "passive"))
      (node (ref "R17") (pin "2") (pinfunction "2_2") (pintype "passive"))
    )
    (net (code "36") (name "Net-(IC1-BOOT)") (class "Default")
      (node (ref "C6") (pin "2") (pinfunction "2_2") (pintype "passive"))
      (node (ref "IC1") (pin "1") (pinfunction "BOOT_1") (pintype "passive"))
    )
    (net (code "37") (name "Net-(IC1-EN)") (class "Default")
      (node (ref "IC1") (pin "3") (pinfunction "EN_3") (pintype "passive"))
      (node (ref "R5") (pin "2") (pinfunction "2_2") (pintype "passive"))
    )
    (net (code "38") (name "Net-(IC1-FB)") (class "Default")
      (node (ref "IC1") (pin "5") (pinfunction "FB_5") (pintype "passive"))
      (node (ref "R13") (pin "1") (pinfunction "1_1") (pintype "passive"))
      (node (ref "R8") (pin "2") (pinfunction "2_2") (pintype "passive"))
    )
    (net (code "39") (name "Net-(IC1-RT{slash}SYNC)") (class "Default")
      (node (ref "IC1") (pin "4") (pinfunction "RT/SYNC_4") (pintype "passive"))
      (node (ref "R10") (pin "2") (pinfunction "2_2") (pintype "passive"))
    )
    (net (code "40") (name "Net-(IC1-SS)") (class "Default")
      (node (ref "C23") (pin "2") (pinfunction "2_2") (pintype "passive"))
      (node (ref "IC1") (pin "6") (pinfunction "SS_6") (pintype "passive"))
    )
    (net (code "41") (name "Net-(IC1-SW)") (class "Default")
      (node (ref "C6") (pin "1") (pinfunction "1_1") (pintype "passive"))
      (node (ref "D2") (pin "2") (pinfunction "2_2") (pintype "passive"))
      (node (ref "IC1") (pin "8") (pinfunction "SW_8") (pintype "passive"))
      (node (ref "L1") (pin "1") (pinfunction "1_1") (pintype "passive"))
    )
    (net (code "42") (name "Net-(IC1-VIN)") (class "Default")
      (node (ref "C8") (pin "1") (pinfunction "1_1") (pintype "passive"))
      (node (ref "C9") (pin "2") (pinfunction "2_2") (pintype "passive"))
      (node (ref "D1") (pin "2") (pinfunction "2_2") (pintype "passive"))
      (node (ref "IC1") (pin "2") (pinfunction "VIN_2") (pintype "passive"))
      (node (ref "R5") (pin "1") (pinfunction "1_1") (pintype "passive"))
    )
    (net (code "43") (name "Net-(IC2-IN)") (class "Default")
      (node (ref "*2") (pin "3") (pintype "passive"))
      (node (ref "C31") (pin "1") (pinfunction "1_1") (pintype "passive"))
      (node (ref "C32") (pin "1") (pinfunction "1_1") (pintype "passive"))
      (node (ref "IC2") (pin "1") (pinfunction "IN_1") (pintype "passive"))
      (node (ref "IC3") (pin "3") (pinfunction "VDD_3") (pintype "passive"))
    )
    (net (code "44") (name "Net-(LED1-Pad1)") (class "Default")
      (node (ref "LED1") (pin "1") (pinfunction "1_1") (pintype "passive"))
      (node (ref "R9") (pin "1") (pinfunction "1_1") (pintype "passive"))
    )
    (net (code "45") (name "Net-(LED2-Pad1)") (class "Default")
      (node (ref "LED2") (pin "1") (pinfunction "1_1") (pintype "passive"))
      (node (ref "R22") (pin "1") (pinfunction "1_1") (pintype "passive"))
    )
    (net (code "46") (name "Net-(LS1-LEAD_-)") (class "Default")
      (node (ref "*3") (pin "2") (pintype "passive"))
      (node (ref "D6") (pin "1") (pinfunction "1_1") (pintype "passive"))
      (node (ref "LS1") (pin "3") (pinfunction "LEAD_-_3") (pintype "passive"))
    )
    (net (code "47") (name "Net-(Q1-B)") (class "Default")
      (node (ref "Q1") (pin "2") (pinfunction "B_2") (pintype "passive"))
      (node (ref "R17") (pin "1") (pinfunction "1_1") (pintype "passive"))
      (node (ref "R18") (pin "1") (pinfunction "1_1") (pintype "passive"))
    )
    (net (code "48") (name "Net-(U1A-IN+)") (class "Default")
      (node (ref "R1") (pin "1") (pinfunction "1_1") (pintype "passive"))
      (node (ref "U1") (pin "3") (pinfunction "IN+_3") (pintype "input"))
    )
    (net (code "49") (name "Net-(U1A-IN-)") (class "Default")
      (node (ref "R2") (pin "2") (pinfunction "2_2") (pintype "passive"))
      (node (ref "U1") (pin "1") (pinfunction "OUT_1") (pintype "output"))
      (node (ref "U1") (pin "2") (pinfunction "IN-_2") (pintype "input"))
    )
    (net (code "50") (name "Net-(U1B-IN+)") (class "Default")
      (node (ref "C3") (pin "2") (pinfunction "2_2") (pintype "passive"))
      (node (ref "R2") (pin "1") (pinfunction "1_1") (pintype "passive"))
      (node (ref "U1") (pin "5") (pinfunction "IN+_5") (pintype "input"))
    )
    (net (code "51") (name "Net-(U1B-IN-)") (class "Default")
      (node (ref "C10") (pin "2") (pinfunction "2_2") (pintype "passive"))
      (node (ref "C21") (pin "1") (pinfunction "1_1") (pintype "passive"))
      (node (ref "R11") (pin "1") (pinfunction "1_1") (pintype "passive"))
      (node (ref "R15") (pin "1") (pinfunction "1_1") (pintype "passive"))
      (node (ref "R4") (pin "1") (pinfunction "1_1") (pintype "passive"))
      (node (ref "R7") (pin "2") (pinfunction "2_2") (pintype "passive"))
      (node (ref "U1") (pin "6") (pinfunction "IN-_6") (pintype "input"))
    )
    (net (code "52") (name "Net-(U2B-IN+)") (class "Default")
      (node (ref "R15") (pin "2") (pinfunction "2_2") (pintype "passive"))
      (node (ref "U2") (pin "5") (pinfunction "IN+_5") (pintype "input"))
    )
    (net (code "53") (name "Net-(U2B-IN-)") (class "Default")
      (node (ref "R12") (pin "2") (pinfunction "2_2") (pintype "passive"))
      (node (ref "U2") (pin "6") (pinfunction "IN-_6") (pintype "input"))
    )
    (net (code "54") (name "Net-(U2B-OUT)") (class "Default")
      (node (ref "R12") (pin "1") (pinfunction "1_1") (pintype "passive"))
      (node (ref "R14") (pin "1") (pinfunction "1_1") (pintype "passive"))
      (node (ref "U2") (pin "7") (pinfunction "OUT_7") (pintype "output"))
    )
    (net (code "55") (name "Net-(WT1-IO0{slash}I2S_MCLK)") (class "Default")
      (node (ref "P1") (pin "2") (pinfunction "2_2") (pintype "passive"))
      (node (ref "WT1") (pin "24") (pinfunction "IO0/I2S_MCLK_24") (pintype "passive"))
    )
    (net (code "56") (name "Net-(WT1-IO33{slash}ADC1_5)") (class "Default")
      (node (ref "R21") (pin "1") (pinfunction "1_1") (pintype "passive"))
      (node (ref "WT1") (pin "31") (pinfunction "IO33/ADC1_5_31") (pintype "passive"))
    )
    (net (code "57") (name "Net-(WT1-TXD)") (class "Default")
      (node (ref "LED2") (pin "2") (pinfunction "2_2") (pintype "passive"))
      (node (ref "WT1") (pin "21") (pinfunction "TXD_21") (pintype "passive"))
    )
    (net (code "58") (name "VCCA") (class "Default")
      (node (ref "C1") (pin "1") (pinfunction "1_1") (pintype "passive"))
      (node (ref "C18") (pin "1") (pinfunction "1_1") (pintype "passive"))
      (node (ref "C19") (pin "1") (pinfunction "1_1") (pintype "passive"))
      (node (ref "C2") (pin "1") (pinfunction "1_1") (pintype "passive"))
      (node (ref "C20") (pin "1") (pinfunction "1_1") (pintype "passive"))
      (node (ref "FL2") (pin "4") (pinfunction "4_4") (pintype "passive"))
      (node (ref "U1") (pin "8") (pinfunction "V+_8") (pintype "power_in"))
      (node (ref "U2") (pin "8") (pinfunction "V+_8") (pintype "power_in"))
    )
    (net (code "59") (name "VREF_pH") (class "Default")
      (node (ref "C5") (pin "2") (pinfunction "2_2") (pintype "passive"))
      (node (ref "J1") (pin "2") (pinfunction "2_2") (pintype "passive"))
      (node (ref "J1") (pin "3") (pinfunction "3_3") (pintype "passive"))
      (node (ref "J1") (pin "4") (pinfunction "4_4") (pintype "passive"))
      (node (ref "J1") (pin "5") (pinfunction "5_5") (pintype "passive"))
      (node (ref "R21") (pin "2") (pinfunction "2_2") (pintype "passive"))
      (node (ref "R3") (pin "2") (pinfunction "2_2") (pintype "passive"))
      (node (ref "U2") (pin "1") (pinfunction "OUT_1") (pintype "output"))
      (node (ref "U2") (pin "2") (pinfunction "IN-_2") (pintype "input"))
    )
    (net (code "60") (name "unconnected-(WT1-ESP32_EN-Pad18)") (class "Default")
      (node (ref "WT1") (pin "18") (pinfunction "ESP32_EN_18") (pintype "passive"))
    )
    (net (code "61") (name "unconnected-(WT1-IO2-Pad12)") (class "Default")
      (node (ref "WT1") (pin "12") (pinfunction "IO2_12") (pintype "passive"))
    )
    (net (code "62") (name "unconnected-(WT1-IO27{slash}ADC2_7-Pad27)") (class "Default")
      (node (ref "WT1") (pin "27") (pinfunction "IO27/ADC2_7_27") (pintype "passive"))
    )
    (net (code "63") (name "unconnected-(WT1-J_IO13-Pad16)") (class "Default")
      (node (ref "WT1") (pin "16") (pinfunction "J_IO13_16") (pintype "passive"))
    )
    (net (code "64") (name "unconnected-(WT1-J_IO14-Pad25)") (class "Default")
      (node (ref "WT1") (pin "25") (pinfunction "J_IO14_25") (pintype "passive"))
    )
    (net (code "65") (name "unconnected-(WT1-J_IO15-Pad14)") (class "Default")
      (node (ref "WT1") (pin "14") (pinfunction "J_IO15_14") (pintype "passive"))
    )
    (net (code "66") (name "unconnected-(WT1-J_IO21-Pad19)") (class "Default")
      (node (ref "WT1") (pin "19") (pinfunction "J_IO21_19") (pintype "passive"))
    )
    (net (code "67") (name "unconnected-(WT1-J_IO22{slash}VSPIWP{slash}HS2-CLK-Pad20)") (class "Default")
      (node (ref "WT1") (pin "20") (pinfunction "J_IO22/VSPIWP/HS2-CLK_20") (pintype "passive"))
    )
    (net (code "68") (name "unconnected-(WT1-J_IO23-Pad22)") (class "Default")
      (node (ref "WT1") (pin "22") (pinfunction "J_IO23_22") (pintype "passive"))
    )
    (net (code "69") (name "unconnected-(WT1-SENSOR_VN-Pad9)") (class "Default")
      (node (ref "WT1") (pin "9") (pinfunction "SENSOR_VN_9") (pintype "passive"))
    )
    (net (code "70") (name "unconnected-(WT1-SENSOR_VP-Pad11)") (class "Default")
      (node (ref "WT1") (pin "11") (pinfunction "SENSOR_VP_11") (pintype "passive"))
    )
  )
)
